# ESP12E_SMD_0603.net
KiCad netlist of a schematic drawn in EAGLE
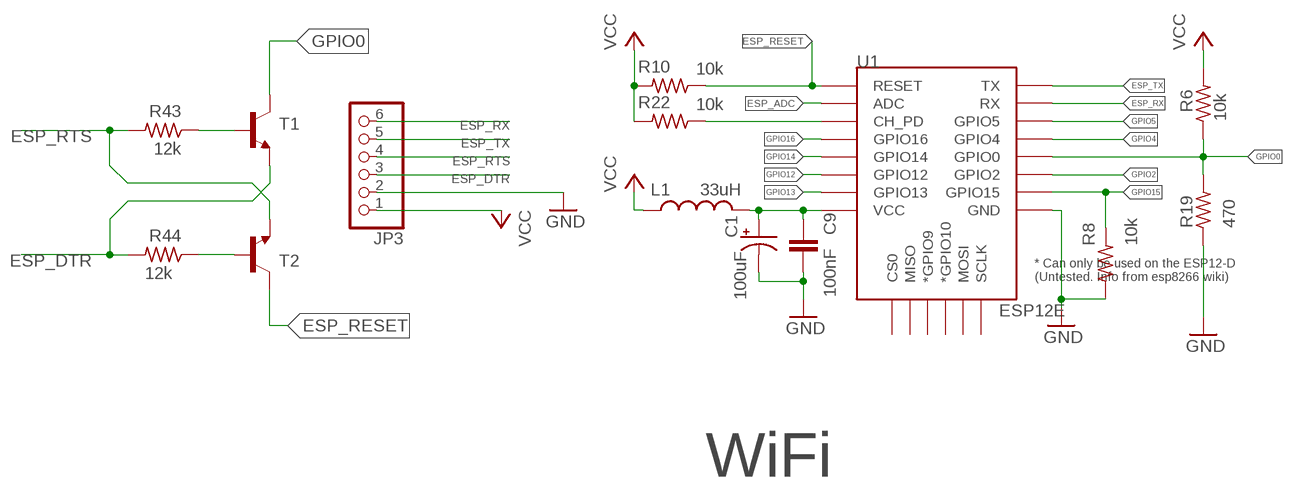
[diagram p0: schematic, sheet 1]

(export (version "E")
  (design (tool "Eeschema 10.0.6"))
  (components
    (comp (ref "C1")
      (value "100uF")
      (footprint "eagle-import:UD-6,3X7,7_NICHICON")
      (libsource (lib "eagle-import") (part "CPOL-USUD-6,3X7,7"))
    )
    (comp (ref "C9")
      (value "100nF")
      (footprint "eagle-import:C0603")
      (libsource (lib "eagle-import") (part "C-EUC0603"))
    )
    (comp (ref "JP3")
      (value "PINHD-1X6")
      (footprint "eagle-import:1X06")
      (libsource (lib "eagle-import") (part "PINHD-1X6"))
    )
    (comp (ref "L1")
      (value "33uH")
      (footprint "eagle-import:L0603")
      (libsource (lib "eagle-import") (part "L-USL0603"))
    )
    (comp (ref "R6")
      (value "10k")
      (footprint "eagle-import:R0603")
      (libsource (lib "eagle-import") (part "R-US_R0603"))
    )
    (comp (ref "R8")
      (value "10k")
      (footprint "eagle-import:R0603")
      (libsource (lib "eagle-import") (part "R-US_R0603"))
    )
    (comp (ref "R10")
      (value "10k")
      (footprint "eagle-import:R0603")
      (libsource (lib "eagle-import") (part "R-US_R0603"))
    )
    (comp (ref "R19")
      (value "470")
      (footprint "eagle-import:R0603")
      (libsource (lib "eagle-import") (part "R-US_R0603"))
    )
    (comp (ref "R22")
      (value "10k")
      (footprint "eagle-import:R0603")
      (libsource (lib "eagle-import") (part "R-US_R0603"))
    )
    (comp (ref "R43")
      (value "12k")
      (footprint "eagle-import:R0603")
      (libsource (lib "eagle-import") (part "R-US_R0603"))
    )
    (comp (ref "R44")
      (value "12k")
      (footprint "eagle-import:R0603")
      (libsource (lib "eagle-import") (part "R-US_R0603"))
    )
    (comp (ref "T1")
      (value "MMBT2222ALT1-NPN-SOT23-BEC")
      (footprint "eagle-import:SOT23-BEC")
      (libsource (lib "eagle-import") (part "-NPN-SOT23-BECMMBT2222ALT1"))
    )
    (comp (ref "T2")
      (value "MMBT2222ALT1-NPN-SOT23-BEC")
      (footprint "eagle-import:SOT23-BEC")
      (libsource (lib "eagle-import") (part "-NPN-SOT23-BECMMBT2222ALT1"))
    )
    (comp (ref "U1")
      (value "ESP12E")
      (footprint "eagle-import:ESP12E-SMD")
      (libsource (lib "eagle-import") (part "ESP12ESMD"))
    )
  )
  (nets
    (net (code "1") (name "/ESP_DTR") (class "Default")
      (node (ref "JP3") (pin "3") (pinfunction "3_3") (pintype "passive"))
      (node (ref "R44") (pin "2") (pinfunction "2_2") (pintype "passive"))
      (node (ref "T1") (pin "E") (pinfunction "E_E") (pintype "passive"))
    )
    (net (code "2") (name "/ESP_RTS") (class "Default")
      (node (ref "JP3") (pin "4") (pinfunction "4_4") (pintype "passive"))
      (node (ref "R43") (pin "2") (pinfunction "2_2") (pintype "passive"))
      (node (ref "T2") (pin "E") (pinfunction "E_E") (pintype "passive"))
    )
    (net (code "3") (name "ESP_ADC") (class "Default")
      (node (ref "U1") (pin "ADC") (pinfunction "ADC_ADC") (pintype "bidirectional"))
    )
    (net (code "4") (name "ESP_RESET") (class "Default")
      (node (ref "R10") (pin "1") (pinfunction "1_1") (pintype "passive"))
      (node (ref "T2") (pin "C") (pinfunction "C_C") (pintype "passive"))
      (node (ref "U1") (pin "RESET") (pinfunction "RESET_RESET") (pintype "bidirectional"))
    )
    (net (code "5") (name "ESP_RX") (class "Default")
      (node (ref "JP3") (pin "6") (pinfunction "6_6") (pintype "passive"))
      (node (ref "U1") (pin "RXD0") (pinfunction "RX_RXD0") (pintype "bidirectional"))
    )
    (net (code "6") (name "ESP_TX") (class "Default")
      (node (ref "JP3") (pin "5") (pinfunction "5_5") (pintype "passive"))
      (node (ref "U1") (pin "TXD0") (pinfunction "TX_TXD0") (pintype "bidirectional"))
    )
    (net (code "7") (name "GND") (class "Default")
      (node (ref "C1") (pin "-") (pinfunction "-_-") (pintype "passive"))
      (node (ref "C9") (pin "2") (pinfunction "2_2") (pintype "passive"))
      (node (ref "JP3") (pin "2") (pinfunction "2_2") (pintype "passive"))
      (node (ref "R19") (pin "1") (pinfunction "1_1") (pintype "passive"))
      (node (ref "R8") (pin "1") (pinfunction "1_1") (pintype "passive"))
      (node (ref "U1") (pin "GND") (pinfunction "GND_GND") (pintype "bidirectional"))
    )
    (net (code "8") (name "GPIO0") (class "Default")
      (node (ref "R19") (pin "2") (pinfunction "2_2") (pintype "passive"))
      (node (ref "R6") (pin "1") (pinfunction "1_1") (pintype "passive"))
      (node (ref "T1") (pin "C") (pinfunction "C_C") (pintype "passive"))
      (node (ref "U1") (pin "GPIO0") (pinfunction "GPIO0_GPIO0") (pintype "bidirectional"))
    )
    (net (code "9") (name "GPIO2") (class "Default")
      (node (ref "U1") (pin "GPIO2") (pinfunction "GPIO2_GPIO2") (pintype "bidirectional"))
    )
    (net (code "10") (name "GPIO4") (class "Default")
      (node (ref "U1") (pin "GPIO4") (pinfunction "GPIO4_GPIO4") (pintype "bidirectional"))
    )
    (net (code "11") (name "GPIO5") (class "Default")
      (node (ref "U1") (pin "GPIO5") (pinfunction "GPIO5_GPIO5") (pintype "bidirectional"))
    )
    (net (code "12") (name "GPIO12") (class "Default")
      (node (ref "U1") (pin "GPIO12") (pinfunction "GPIO12_GPIO12") (pintype "bidirectional"))
    )
    (net (code "13") (name "GPIO13") (class "Default")
      (node (ref "U1") (pin "GPIO13") (pinfunction "GPIO13_GPIO13") (pintype "bidirectional"))
    )
    (net (code "14") (name "GPIO14") (class "Default")
      (node (ref "U1") (pin "GPIO14") (pinfunction "GPIO14_GPIO14") (pintype "bidirectional"))
    )
    (net (code "15") (name "GPIO15") (class "Default")
      (node (ref "R8") (pin "2") (pinfunction "2_2") (pintype "passive"))
      (node (ref "U1") (pin "GPIO15") (pinfunction "GPIO15_GPIO15") (pintype "bidirectional"))
    )
    (net (code "16") (name "GPIO16") (class "Default")
      (node (ref "U1") (pin "GPIO16") (pinfunction "GPIO16_GPIO16") (pintype "bidirectional"))
    )
    (net (code "17") (name "Net-(C1-Pad+)") (class "Default")
      (node (ref "C1") (pin "+") (pinfunction "+_+") (pintype "passive"))
      (node (ref "C9") (pin "1") (pinfunction "1_1") (pintype "passive"))
      (node (ref "L1") (pin "2") (pinfunction "2_2") (pintype "passive"))
      (node (ref "U1") (pin "VCC") (pinfunction "VCC_VCC") (pintype "bidirectional"))
    )
    (net (code "18") (name "Net-(R22-Pad1)") (class "Default")
      (node (ref "R22") (pin "1") (pinfunction "1_1") (pintype "passive"))
      (node (ref "U1") (pin "CH_PD") (pinfunction "CH_PD_CH_PD") (pintype "bidirectional"))
    )
    (net (code "19") (name "Net-(R43-Pad1)") (class "Default")
      (node (ref "R43") (pin "1") (pinfunction "1_1") (pintype "passive"))
      (node (ref "T1") (pin "B") (pinfunction "B_B") (pintype "passive"))
    )
    (net (code "20") (name "Net-(R44-Pad1)") (class "Default")
      (node (ref "R44") (pin "1") (pinfunction "1_1") (pintype "passive"))
      (node (ref "T2") (pin "B") (pinfunction "B_B") (pintype "passive"))
    )
    (net (code "21") (name "VCC") (class "Default")
      (node (ref "JP3") (pin "1") (pinfunction "1_1") (pintype "passive"))
      (node (ref "L1") (pin "1") (pinfunction "1_1") (pintype "passive"))
      (node (ref "R10") (pin "2") (pinfunction "2_2") (pintype "passive"))
      (node (ref "R22") (pin "2") (pinfunction "2_2") (pintype "passive"))
      (node (ref "R6") (pin "2") (pinfunction "2_2") (pintype "passive"))
    )
    (net (code "22") (name "unconnected-(U1-*GPIO9-PadGPIO9)") (class "Default")
      (node (ref "U1") (pin "GPIO9") (pinfunction "*GPIO9_GPIO9") (pintype "bidirectional"))
    )
    (net (code "23") (name "unconnected-(U1-*GPIO10-PadGPIO10)") (class "Default")
      (node (ref "U1") (pin "GPIO10") (pinfunction "*GPIO10_GPIO10") (pintype "bidirectional"))
    )
    (net (code "24") (name "unconnected-(U1-PadCS0)") (class "Default")
      (node (ref "U1") (pin "CS0") (pinfunction "CS0_CS0") (pintype "bidirectional"))
    )
    (net (code "25") (name "unconnected-(U1-PadMISO)") (class "Default")
      (node (ref "U1") (pin "MISO") (pinfunction "MISO_MISO") (pintype "bidirectional"))
    )
    (net (code "26") (name "unconnected-(U1-PadMOSI)") (class "Default")
      (node (ref "U1") (pin "MOSI") (pinfunction "MOSI_MOSI") (pintype "bidirectional"))
    )
    (net (code "27") (name "unconnected-(U1-PadSCLK)") (class "Default")
      (node (ref "U1") (pin "SCLK") (pinfunction "SCLK_SCLK") (pintype "bidirectional"))
    )
  )
)
